# ASD2123.net
KiCad netlist of a schematic drawn in EAGLE
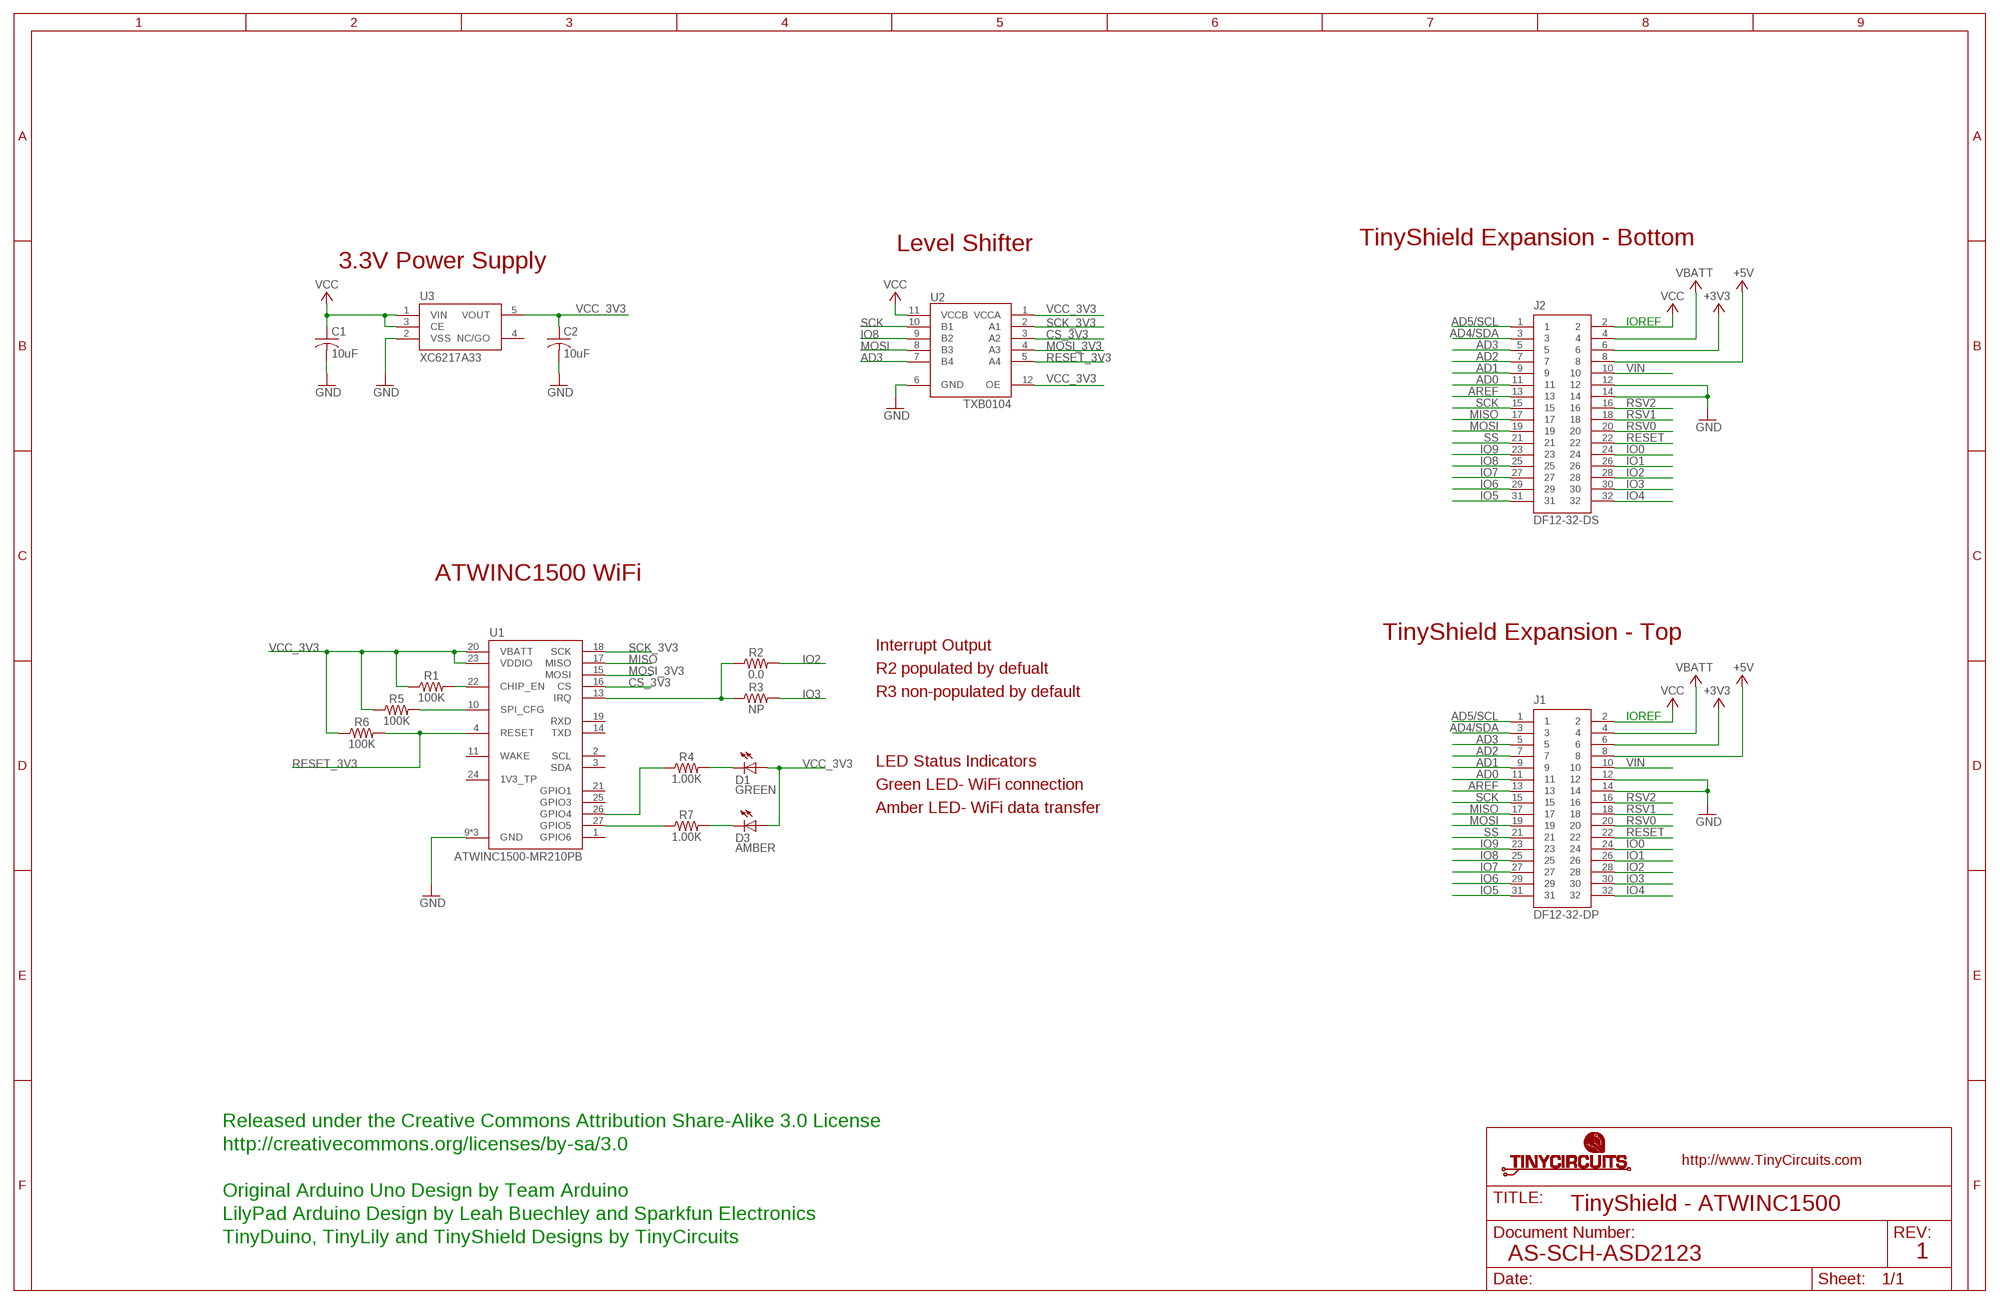
[diagram p0: schematic, sheet 1]

(export (version "E")
  (design (tool "Eeschema 10.0.6"))
  (components
    (comp (ref "C1")
      (value "10uF")
      (footprint "eagle-import:C0603")
      (fields (field (name "PARTNO") "AS-ITM-00002") (field (name "PARTNO_1") "AS-ITM-00002"))
      (libsource (lib "eagle-import") (part "AS-ITM-00002"))
    )
    (comp (ref "C2")
      (value "10uF")
      (footprint "eagle-import:C0603")
      (fields (field (name "PARTNO") "AS-ITM-00002") (field (name "PARTNO_1") "AS-ITM-00002"))
      (libsource (lib "eagle-import") (part "AS-ITM-00002"))
    )
    (comp (ref "D1")
      (value "GREEN")
      (footprint "eagle-import:0402_LED")
      (fields (field (name "PARTNO") "AS-ITM-00038"))
      (libsource (lib "eagle-import") (part "AS-ITM-00038"))
    )
    (comp (ref "D3")
      (value "AMBER")
      (footprint "eagle-import:0402_LED")
      (fields (field (name "PARTNO") "AS-ITM-00058"))
      (libsource (lib "eagle-import") (part "AS-ITM-00058"))
    )
    (comp (ref "J1")
      (value "DF12-32-DP")
      (footprint "eagle-import:DF12-32-DP")
      (fields (field (name "PARTNO") "AS-ITM-00015") (field (name "PARTNO_1") "AS-ITM-00015"))
      (libsource (lib "eagle-import") (part "AS-ITM-00015"))
    )
    (comp (ref "J2")
      (value "DF12-32-DS")
      (footprint "eagle-import:DF12-32-DS")
      (fields (field (name "PARTNO") "AS-ITM-00012") (field (name "PARTNO_1") "AS-ITM-00012"))
      (libsource (lib "eagle-import") (part "AS-ITM-00012"))
    )
    (comp (ref "R1")
      (value "100K")
      (footprint "eagle-import:0402")
      (fields (field (name "PARTNO") "AS-ITM-00004"))
      (libsource (lib "eagle-import") (part "AS-ITM-00004"))
    )
    (comp (ref "R2")
      (value "0.0")
      (footprint "eagle-import:0402")
      (fields (field (name "PARTNO") "AS-ITM-00076") (field (name "PARTNO_1") "AS-ITM-00076"))
      (libsource (lib "eagle-import") (part "AS-ITM-00076"))
    )
    (comp (ref "R3")
      (value "NP")
      (footprint "eagle-import:0402")
      (fields (field (name "PARTNO") "AS-ITM-00076") (field (name "PARTNO_1") "AS-ITM-00076"))
      (libsource (lib "eagle-import") (part "AS-ITM-00076"))
    )
    (comp (ref "R4")
      (value "1.00K")
      (footprint "eagle-import:0402")
      (fields (field (name "PARTNO") "AS-ITM-00003"))
      (libsource (lib "eagle-import") (part "AS-ITM-00003"))
    )
    (comp (ref "R5")
      (value "100K")
      (footprint "eagle-import:0402")
      (fields (field (name "PARTNO") "AS-ITM-00004"))
      (libsource (lib "eagle-import") (part "AS-ITM-00004"))
    )
    (comp (ref "R6")
      (value "100K")
      (footprint "eagle-import:0402")
      (fields (field (name "PARTNO") "AS-ITM-00004"))
      (libsource (lib "eagle-import") (part "AS-ITM-00004"))
    )
    (comp (ref "R7")
      (value "1.00K")
      (footprint "eagle-import:0402")
      (fields (field (name "PARTNO") "AS-ITM-00003"))
      (libsource (lib "eagle-import") (part "AS-ITM-00003"))
    )
    (comp (ref "U1")
      (value "ATWINC1500-MR210PB")
      (footprint "eagle-import:ATWINC1500-MR210PB")
      (fields (field (name "PARTNO") "AS-ITM-00292"))
      (libsource (lib "eagle-import") (part "AS-ITM-00292"))
    )
    (comp (ref "U2")
      (value "TXB0104")
      (footprint "eagle-import:UQFN-12")
      (fields (field (name "PARTNO") "AS-ITM-00048"))
      (libsource (lib "eagle-import") (part "AS-ITM-00048"))
    )
    (comp (ref "U3")
      (value "XC6217A33")
      (footprint "eagle-import:SOT-25")
      (fields (field (name "PARTNO") "AS-ITM-00046") (field (name "PARTNO_1") "AS-ITM-00046"))
      (libsource (lib "eagle-import") (part "AS-ITM-00046"))
    )
  )
  (nets
    (net (code "1") (name "+3V3") (class "Default")
      (node (ref "J1") (pin "6") (pinfunction "6_6") (pintype "bidirectional"))
      (node (ref "J2") (pin "6") (pinfunction "6_6") (pintype "bidirectional"))
    )
    (net (code "2") (name "+5V") (class "Default")
      (node (ref "J1") (pin "8") (pinfunction "8_8") (pintype "bidirectional"))
      (node (ref "J2") (pin "8") (pinfunction "8_8") (pintype "bidirectional"))
    )
    (net (code "3") (name "/AD0") (class "Default")
      (node (ref "J1") (pin "11") (pinfunction "11_11") (pintype "bidirectional"))
      (node (ref "J2") (pin "11") (pinfunction "11_11") (pintype "bidirectional"))
    )
    (net (code "4") (name "/AD1") (class "Default")
      (node (ref "J1") (pin "9") (pinfunction "9_9") (pintype "bidirectional"))
      (node (ref "J2") (pin "9") (pinfunction "9_9") (pintype "bidirectional"))
    )
    (net (code "5") (name "/AD2") (class "Default")
      (node (ref "J1") (pin "7") (pinfunction "7_7") (pintype "bidirectional"))
      (node (ref "J2") (pin "7") (pinfunction "7_7") (pintype "bidirectional"))
    )
    (net (code "6") (name "/AD3") (class "Default")
      (node (ref "J1") (pin "5") (pinfunction "5_5") (pintype "bidirectional"))
      (node (ref "J2") (pin "5") (pinfunction "5_5") (pintype "bidirectional"))
      (node (ref "U2") (pin "7") (pinfunction "B4_7") (pintype "bidirectional"))
    )
    (net (code "7") (name "/AD4{slash}SDA") (class "Default")
      (node (ref "J1") (pin "3") (pinfunction "3_3") (pintype "bidirectional"))
      (node (ref "J2") (pin "3") (pinfunction "3_3") (pintype "bidirectional"))
    )
    (net (code "8") (name "/AD5{slash}SCL") (class "Default")
      (node (ref "J1") (pin "1") (pinfunction "1_1") (pintype "bidirectional"))
      (node (ref "J2") (pin "1") (pinfunction "1_1") (pintype "bidirectional"))
    )
    (net (code "9") (name "/AREF") (class "Default")
      (node (ref "J1") (pin "13") (pinfunction "13_13") (pintype "bidirectional"))
      (node (ref "J2") (pin "13") (pinfunction "13_13") (pintype "bidirectional"))
    )
    (net (code "10") (name "/CS_3V3") (class "Default")
      (node (ref "U1") (pin "16") (pinfunction "CS_16") (pintype "bidirectional"))
      (node (ref "U2") (pin "3") (pinfunction "A2_3") (pintype "bidirectional"))
    )
    (net (code "11") (name "/IO0") (class "Default")
      (node (ref "J1") (pin "24") (pinfunction "24_24") (pintype "bidirectional"))
      (node (ref "J2") (pin "24") (pinfunction "24_24") (pintype "bidirectional"))
    )
    (net (code "12") (name "/IO1") (class "Default")
      (node (ref "J1") (pin "26") (pinfunction "26_26") (pintype "bidirectional"))
      (node (ref "J2") (pin "26") (pinfunction "26_26") (pintype "bidirectional"))
    )
    (net (code "13") (name "/IO2") (class "Default")
      (node (ref "J1") (pin "28") (pinfunction "28_28") (pintype "bidirectional"))
      (node (ref "J2") (pin "28") (pinfunction "28_28") (pintype "bidirectional"))
      (node (ref "R2") (pin "2") (pinfunction "2_2") (pintype "passive"))
    )
    (net (code "14") (name "/IO3") (class "Default")
      (node (ref "J1") (pin "30") (pinfunction "30_30") (pintype "bidirectional"))
      (node (ref "J2") (pin "30") (pinfunction "30_30") (pintype "bidirectional"))
      (node (ref "R3") (pin "2") (pinfunction "2_2") (pintype "passive"))
    )
    (net (code "15") (name "/IO4") (class "Default")
      (node (ref "J1") (pin "32") (pinfunction "32_32") (pintype "bidirectional"))
      (node (ref "J2") (pin "32") (pinfunction "32_32") (pintype "bidirectional"))
    )
    (net (code "16") (name "/IO5") (class "Default")
      (node (ref "J1") (pin "31") (pinfunction "31_31") (pintype "bidirectional"))
      (node (ref "J2") (pin "31") (pinfunction "31_31") (pintype "bidirectional"))
    )
    (net (code "17") (name "/IO6") (class "Default")
      (node (ref "J1") (pin "29") (pinfunction "29_29") (pintype "bidirectional"))
      (node (ref "J2") (pin "29") (pinfunction "29_29") (pintype "bidirectional"))
    )
    (net (code "18") (name "/IO7") (class "Default")
      (node (ref "J1") (pin "27") (pinfunction "27_27") (pintype "bidirectional"))
      (node (ref "J2") (pin "27") (pinfunction "27_27") (pintype "bidirectional"))
    )
    (net (code "19") (name "/IO8") (class "Default")
      (node (ref "J1") (pin "25") (pinfunction "25_25") (pintype "bidirectional"))
      (node (ref "J2") (pin "25") (pinfunction "25_25") (pintype "bidirectional"))
      (node (ref "U2") (pin "9") (pinfunction "B2_9") (pintype "bidirectional"))
    )
    (net (code "20") (name "/IO9") (class "Default")
      (node (ref "J1") (pin "23") (pinfunction "23_23") (pintype "bidirectional"))
      (node (ref "J2") (pin "23") (pinfunction "23_23") (pintype "bidirectional"))
    )
    (net (code "21") (name "/MISO") (class "Default")
      (node (ref "J1") (pin "17") (pinfunction "17_17") (pintype "bidirectional"))
      (node (ref "J2") (pin "17") (pinfunction "17_17") (pintype "bidirectional"))
      (node (ref "U1") (pin "17") (pinfunction "MISO_17") (pintype "bidirectional"))
    )
    (net (code "22") (name "/MOSI") (class "Default")
      (node (ref "J1") (pin "19") (pinfunction "19_19") (pintype "bidirectional"))
      (node (ref "J2") (pin "19") (pinfunction "19_19") (pintype "bidirectional"))
      (node (ref "U2") (pin "8") (pinfunction "B3_8") (pintype "bidirectional"))
    )
    (net (code "23") (name "/MOSI_3V3") (class "Default")
      (node (ref "U1") (pin "15") (pinfunction "MOSI_15") (pintype "bidirectional"))
      (node (ref "U2") (pin "4") (pinfunction "A3_4") (pintype "bidirectional"))
    )
    (net (code "24") (name "/RESET") (class "Default")
      (node (ref "J1") (pin "22") (pinfunction "22_22") (pintype "bidirectional"))
      (node (ref "J2") (pin "22") (pinfunction "22_22") (pintype "bidirectional"))
    )
    (net (code "25") (name "/RESET_3V3") (class "Default")
      (node (ref "R6") (pin "2") (pinfunction "2_2") (pintype "passive"))
      (node (ref "U1") (pin "4") (pinfunction "RESET_4") (pintype "bidirectional"))
      (node (ref "U2") (pin "5") (pinfunction "A4_5") (pintype "bidirectional"))
    )
    (net (code "26") (name "/RSV0") (class "Default")
      (node (ref "J1") (pin "20") (pinfunction "20_20") (pintype "bidirectional"))
      (node (ref "J2") (pin "20") (pinfunction "20_20") (pintype "bidirectional"))
    )
    (net (code "27") (name "/RSV1") (class "Default")
      (node (ref "J1") (pin "18") (pinfunction "18_18") (pintype "bidirectional"))
      (node (ref "J2") (pin "18") (pinfunction "18_18") (pintype "bidirectional"))
    )
    (net (code "28") (name "/RSV2") (class "Default")
      (node (ref "J1") (pin "16") (pinfunction "16_16") (pintype "bidirectional"))
      (node (ref "J2") (pin "16") (pinfunction "16_16") (pintype "bidirectional"))
    )
    (net (code "29") (name "/SCK") (class "Default")
      (node (ref "J1") (pin "15") (pinfunction "15_15") (pintype "bidirectional"))
      (node (ref "J2") (pin "15") (pinfunction "15_15") (pintype "bidirectional"))
      (node (ref "U2") (pin "10") (pinfunction "B1_10") (pintype "bidirectional"))
    )
    (net (code "30") (name "/SCK_3V3") (class "Default")
      (node (ref "U1") (pin "18") (pinfunction "SCK_18") (pintype "bidirectional"))
      (node (ref "U2") (pin "2") (pinfunction "A1_2") (pintype "bidirectional"))
    )
    (net (code "31") (name "/SS") (class "Default")
      (node (ref "J1") (pin "21") (pinfunction "21_21") (pintype "bidirectional"))
      (node (ref "J2") (pin "21") (pinfunction "21_21") (pintype "bidirectional"))
    )
    (net (code "32") (name "/VCC_3V3") (class "Default")
      (node (ref "C2") (pin "1") (pinfunction "1_1") (pintype "passive"))
      (node (ref "D1") (pin "1") (pinfunction "A_1") (pintype "passive"))
      (node (ref "D3") (pin "1") (pinfunction "A_1") (pintype "passive"))
      (node (ref "R1") (pin "1") (pinfunction "1_1") (pintype "passive"))
      (node (ref "R5") (pin "1") (pinfunction "1_1") (pintype "passive"))
      (node (ref "R6") (pin "1") (pinfunction "1_1") (pintype "passive"))
      (node (ref "U1") (pin "20") (pinfunction "VBATT_20") (pintype "bidirectional"))
      (node (ref "U1") (pin "23") (pinfunction "VDDIO_23") (pintype "bidirectional"))
      (node (ref "U2") (pin "1") (pinfunction "VCCA_1") (pintype "bidirectional"))
      (node (ref "U2") (pin "12") (pinfunction "OE_12") (pintype "bidirectional"))
      (node (ref "U3") (pin "5") (pinfunction "VOUT_5") (pintype "bidirectional"))
    )
    (net (code "33") (name "/VIN") (class "Default")
      (node (ref "J1") (pin "10") (pinfunction "10_10") (pintype "bidirectional"))
      (node (ref "J2") (pin "10") (pinfunction "10_10") (pintype "bidirectional"))
    )
    (net (code "34") (name "GND") (class "Default")
      (node (ref "C1") (pin "2") (pinfunction "2_2") (pintype "passive"))
      (node (ref "C2") (pin "2") (pinfunction "2_2") (pintype "passive"))
      (node (ref "J1") (pin "12") (pinfunction "12_12") (pintype "bidirectional"))
      (node (ref "J1") (pin "14") (pinfunction "14_14") (pintype "bidirectional"))
      (node (ref "J2") (pin "12") (pinfunction "12_12") (pintype "bidirectional"))
      (node (ref "J2") (pin "14") (pinfunction "14_14") (pintype "bidirectional"))
      (node (ref "U1") (pin "12") (pinfunction "GND_12") (pintype "bidirectional"))
      (node (ref "U1") (pin "28") (pinfunction "GND_28") (pintype "bidirectional"))
      (node (ref "U1") (pin "9") (pinfunction "GND_9") (pintype "bidirectional"))
      (node (ref "U2") (pin "6") (pinfunction "GND_6") (pintype "bidirectional"))
      (node (ref "U3") (pin "2") (pinfunction "VSS_2") (pintype "power_in"))
    )
    (net (code "35") (name "Net-(D1-C)") (class "Default")
      (node (ref "D1") (pin "2") (pinfunction "C_2") (pintype "passive"))
      (node (ref "R4") (pin "2") (pinfunction "2_2") (pintype "passive"))
    )
    (net (code "36") (name "Net-(D3-C)") (class "Default")
      (node (ref "D3") (pin "2") (pinfunction "C_2") (pintype "passive"))
      (node (ref "R7") (pin "2") (pinfunction "2_2") (pintype "passive"))
    )
    (net (code "37") (name "Net-(U1-CHIP_EN)") (class "Default")
      (node (ref "R1") (pin "2") (pinfunction "2_2") (pintype "passive"))
      (node (ref "U1") (pin "22") (pinfunction "CHIP_EN_22") (pintype "bidirectional"))
    )
    (net (code "38") (name "Net-(U1-GPIO4)") (class "Default")
      (node (ref "R4") (pin "1") (pinfunction "1_1") (pintype "passive"))
      (node (ref "U1") (pin "26") (pinfunction "GPIO4_26") (pintype "bidirectional"))
    )
    (net (code "39") (name "Net-(U1-GPIO5)") (class "Default")
      (node (ref "R7") (pin "1") (pinfunction "1_1") (pintype "passive"))
      (node (ref "U1") (pin "27") (pinfunction "GPIO5_27") (pintype "bidirectional"))
    )
    (net (code "40") (name "Net-(U1-IRQ)") (class "Default")
      (node (ref "R2") (pin "1") (pinfunction "1_1") (pintype "passive"))
      (node (ref "R3") (pin "1") (pinfunction "1_1") (pintype "passive"))
      (node (ref "U1") (pin "13") (pinfunction "IRQ_13") (pintype "bidirectional"))
    )
    (net (code "41") (name "Net-(U1-SPI_CFG)") (class "Default")
      (node (ref "R5") (pin "2") (pinfunction "2_2") (pintype "passive"))
      (node (ref "U1") (pin "10") (pinfunction "SPI_CFG_10") (pintype "bidirectional"))
    )
    (net (code "42") (name "VBATT") (class "Default")
      (node (ref "J1") (pin "4") (pinfunction "4_4") (pintype "bidirectional"))
      (node (ref "J2") (pin "4") (pinfunction "4_4") (pintype "bidirectional"))
    )
    (net (code "43") (name "VCC") (class "Default")
      (node (ref "C1") (pin "1") (pinfunction "1_1") (pintype "passive"))
      (node (ref "J1") (pin "2") (pinfunction "2_2") (pintype "bidirectional"))
      (node (ref "J2") (pin "2") (pinfunction "2_2") (pintype "bidirectional"))
      (node (ref "U2") (pin "11") (pinfunction "VCCB_11") (pintype "bidirectional"))
      (node (ref "U3") (pin "1") (pinfunction "VIN_1") (pintype "bidirectional"))
      (node (ref "U3") (pin "3") (pinfunction "CE_3") (pintype "bidirectional"))
    )
    (net (code "44") (name "unconnected-(U1-1V3_TP-Pad24)") (class "Default")
      (node (ref "U1") (pin "24") (pinfunction "1V3_TP_24") (pintype "bidirectional"))
    )
    (net (code "45") (name "unconnected-(U1-GPIO1-Pad21)") (class "Default")
      (node (ref "U1") (pin "21") (pinfunction "GPIO1_21") (pintype "bidirectional"))
    )
    (net (code "46") (name "unconnected-(U1-GPIO3-Pad25)") (class "Default")
      (node (ref "U1") (pin "25") (pinfunction "GPIO3_25") (pintype "bidirectional"))
    )
    (net (code "47") (name "unconnected-(U1-GPIO6-Pad1)") (class "Default")
      (node (ref "U1") (pin "1") (pinfunction "GPIO6_1") (pintype "bidirectional"))
    )
    (net (code "48") (name "unconnected-(U1-RXD-Pad19)") (class "Default")
      (node (ref "U1") (pin "19") (pinfunction "RXD_19") (pintype "bidirectional"))
    )
    (net (code "49") (name "unconnected-(U1-SCL-Pad2)") (class "Default")
      (node (ref "U1") (pin "2") (pinfunction "SCL_2") (pintype "bidirectional"))
    )
    (net (code "50") (name "unconnected-(U1-SDA-Pad3)") (class "Default")
      (node (ref "U1") (pin "3") (pinfunction "SDA_3") (pintype "bidirectional"))
    )
    (net (code "51") (name "unconnected-(U1-TXD-Pad14)") (class "Default")
      (node (ref "U1") (pin "14") (pinfunction "TXD_14") (pintype "bidirectional"))
    )
    (net (code "52") (name "unconnected-(U1-WAKE-Pad11)") (class "Default")
      (node (ref "U1") (pin "11") (pinfunction "WAKE_11") (pintype "bidirectional"))
    )
    (net (code "53") (name "unconnected-(U3-NC{slash}GO-Pad4)") (class "Default")
      (node (ref "U3") (pin "4") (pinfunction "NC/GO_4") (pintype "bidirectional"))
    )
  )
)
